# Power.net
KiCad netlist of a schematic drawn in Altium Designer
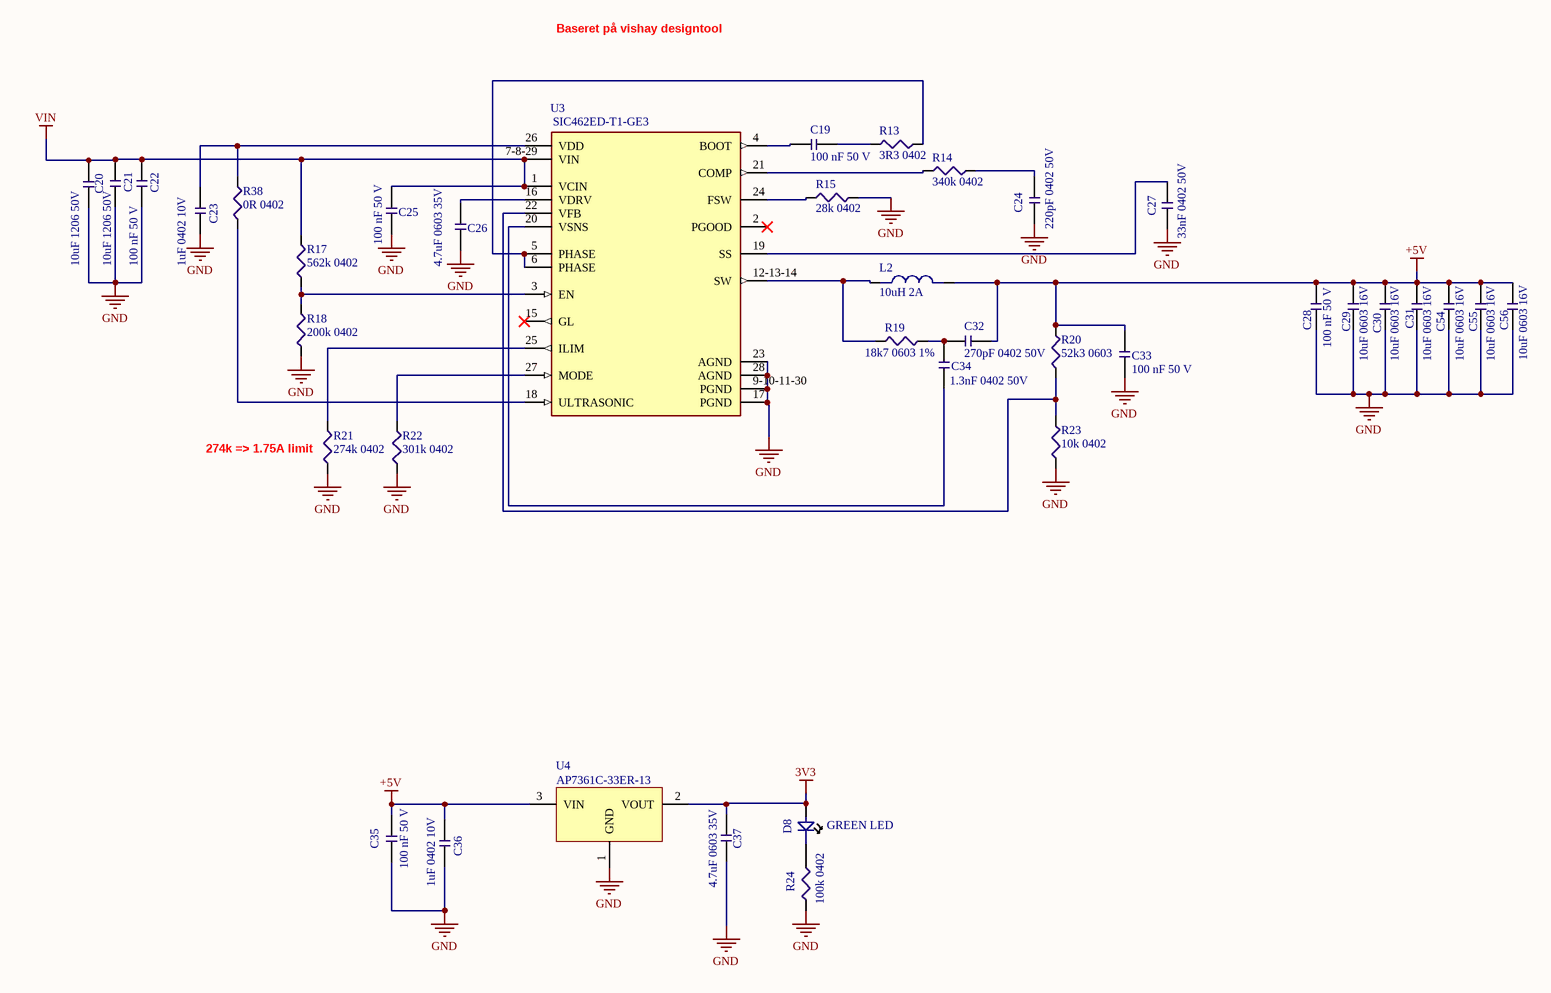
[diagram p0: Power.SchDoc]

(export (version "E")
  (design (tool "Eeschema 10.0.6"))
  (components
    (comp (ref "C19")
      (value "100 nF 50 V")
      (footprint "CAP_0402")
      (description "Multilayer Ceramic Capacitors MLCC - SMD/SMT .1uF 50Volts X7R +/-10% 0402 STD")
      (fields (field (name "TOLERANCE") "10%") (field (name "VOLTAGE") "50 V"))
      (libsource (lib "ON Development Vault") (part "Capacitor"))
    )
    (comp (ref "C20")
      (value "10uF 1206 50V")
      (footprint "CAP_1206")
      (description "10uF 1206 50V X5R 20%")
      (fields (field (name "TOLERANCE") "+/- 20%") (field (name "VOLTAGE") "50 V"))
      (libsource (lib "ON Development Vault") (part "Capacitor"))
    )
    (comp (ref "C21")
      (value "10uF 1206 50V")
      (footprint "CAP_1206")
      (description "10uF 1206 50V X5R 20%")
      (fields (field (name "TOLERANCE") "+/- 20%") (field (name "VOLTAGE") "50 V"))
      (libsource (lib "ON Development Vault") (part "Capacitor"))
    )
    (comp (ref "C22")
      (value "100 nF 50 V")
      (footprint "CAP_0402")
      (description "Multilayer Ceramic Capacitors MLCC - SMD/SMT .1uF 50Volts X7R +/-10% 0402 STD")
      (fields (field (name "TOLERANCE") "10%") (field (name "VOLTAGE") "50 V"))
      (libsource (lib "ON Development Vault") (part "Capacitor"))
    )
    (comp (ref "C23")
      (value "1uF 0402 10V")
      (footprint "CAP_0402")
      (description "1uF 0402 10V 10% X5R")
      (fields (field (name "TOLERANCE") "10%") (field (name "VOLTAGE") "10 V"))
      (libsource (lib "ON Development Vault") (part "Capacitor"))
    )
    (comp (ref "C24")
      (value "220pF 0402 50V")
      (footprint "CAP_0402")
      (description "220pF 0402 50V 5%")
      (fields (field (name "TOLERANCE") "5%") (field (name "VOLTAGE") "50V"))
      (libsource (lib "ON Development Vault") (part "Capacitor"))
    )
    (comp (ref "C25")
      (value "100 nF 50 V")
      (footprint "CAP_0402")
      (description "Multilayer Ceramic Capacitors MLCC - SMD/SMT .1uF 50Volts X7R +/-10% 0402 STD")
      (fields (field (name "TOLERANCE") "10%") (field (name "VOLTAGE") "50 V"))
      (libsource (lib "ON Development Vault") (part "Capacitor"))
    )
    (comp (ref "C26")
      (value "4.7uF 0603 35V")
      (footprint "CAP_0603")
      (fields (field (name "TOLERANCE") "10%"))
      (libsource (lib "ON Development Vault") (part "Capacitor"))
    )
    (comp (ref "C27")
      (value "33nF 0402 50V")
      (footprint "CAP_0402")
      (description "33nF 0402 50V X7R 10%")
      (fields (field (name "TOLERANCE") "10%") (field (name "VOLTAGE") "50V"))
      (libsource (lib "ON Development Vault") (part "Capacitor"))
    )
    (comp (ref "C28")
      (value "100 nF 50 V")
      (footprint "CAP_0402")
      (description "Multilayer Ceramic Capacitors MLCC - SMD/SMT .1uF 50Volts X7R +/-10% 0402 STD")
      (fields (field (name "TOLERANCE") "10%") (field (name "VOLTAGE") "50 V"))
      (libsource (lib "ON Development Vault") (part "Capacitor"))
    )
    (comp (ref "C29")
      (value "10uF 0603 16V")
      (footprint "CAP_0603")
      (description "CAP CER 10UF 16V X5R 0603")
      (fields (field (name "TOLERANCE") "10%") (field (name "VOLTAGE") "16V"))
      (libsource (lib "ON Development Vault") (part "Capacitor"))
    )
    (comp (ref "C30")
      (value "10uF 0603 16V")
      (footprint "CAP_0603")
      (description "CAP CER 10UF 16V X5R 0603")
      (fields (field (name "TOLERANCE") "10%") (field (name "VOLTAGE") "16V"))
      (libsource (lib "ON Development Vault") (part "Capacitor"))
    )
    (comp (ref "C31")
      (value "10uF 0603 16V")
      (footprint "CAP_0603")
      (description "CAP CER 10UF 16V X5R 0603")
      (fields (field (name "TOLERANCE") "10%") (field (name "VOLTAGE") "16V"))
      (libsource (lib "ON Development Vault") (part "Capacitor"))
    )
    (comp (ref "C32")
      (value "270pF 0402 50V")
      (footprint "CAP_0402")
      (description "Multilayer Ceramic Capacitors MLCC - SMD/SMT Midhigh 0402 C0G 50V 270pF 5%")
      (fields (field (name "TOLERANCE") "5%") (field (name "VOLTAGE") "50V"))
      (libsource (lib "ON Development Vault") (part "Capacitor"))
    )
    (comp (ref "C33")
      (value "100 nF 50 V")
      (footprint "CAP_0402")
      (description "Multilayer Ceramic Capacitors MLCC - SMD/SMT .1uF 50Volts X7R +/-10% 0402 STD")
      (fields (field (name "TOLERANCE") "10%") (field (name "VOLTAGE") "50 V"))
      (libsource (lib "ON Development Vault") (part "Capacitor"))
    )
    (comp (ref "C34")
      (value "1.3nF 0402 50V")
      (footprint "CAP_0402")
      (description "Cap Ceramic 0.0013uF 50V C0G 5% SMD 0402 125°C Paper T/R")
      (fields (field (name "TOLERANCE") "10%") (field (name "VOLTAGE") "50V"))
      (libsource (lib "ON Development Vault") (part "Capacitor"))
    )
    (comp (ref "C35")
      (value "100 nF 50 V")
      (footprint "CAP_0402")
      (description "Multilayer Ceramic Capacitors MLCC - SMD/SMT .1uF 50Volts X7R +/-10% 0402 STD")
      (fields (field (name "TOLERANCE") "10%") (field (name "VOLTAGE") "50 V"))
      (libsource (lib "ON Development Vault") (part "Capacitor"))
    )
    (comp (ref "C36")
      (value "1uF 0402 10V")
      (footprint "CAP_0402")
      (description "1uF 0402 10V 10% X5R")
      (fields (field (name "TOLERANCE") "10%") (field (name "VOLTAGE") "10 V"))
      (libsource (lib "ON Development Vault") (part "Capacitor"))
    )
    (comp (ref "C37")
      (value "4.7uF 0603 35V")
      (footprint "CAP_0603")
      (fields (field (name "TOLERANCE") "10%"))
      (libsource (lib "ON Development Vault") (part "Capacitor"))
    )
    (comp (ref "C54")
      (value "10uF 0603 16V")
      (footprint "CAP_0603")
      (description "CAP CER 10UF 16V X5R 0603")
      (fields (field (name "TOLERANCE") "10%") (field (name "VOLTAGE") "16V"))
      (libsource (lib "ON Development Vault") (part "Capacitor"))
    )
    (comp (ref "C55")
      (value "10uF 0603 16V")
      (footprint "CAP_0603")
      (description "CAP CER 10UF 16V X5R 0603")
      (fields (field (name "TOLERANCE") "10%") (field (name "VOLTAGE") "16V"))
      (libsource (lib "ON Development Vault") (part "Capacitor"))
    )
    (comp (ref "C56")
      (value "10uF 0603 16V")
      (footprint "CAP_0603")
      (description "CAP CER 10UF 16V X5R 0603")
      (fields (field (name "TOLERANCE") "10%") (field (name "VOLTAGE") "16V"))
      (libsource (lib "ON Development Vault") (part "Capacitor"))
    )
    (comp (ref "D8")
      (value "GREEN LED")
      (footprint "0402 LED")
      (description "0402 SMD LED")
      (fields (field (name "MFG. PART NUMBER") "LTST-C281KGKT"))
      (libsource (lib "ON Development Vault") (part "LED"))
    )
    (comp (ref "L2")
      (value "10uH 2A")
      (footprint "FP-NR5040-H_4_1-MFG")
      (description "Inductor Power Shielded Wirewound 10uH 20% 100KHz Ferrite 2.1A 0.0728Ohm DCR T/R")
      (fields (field (name "MFG. PART NO") "NRS5040T100MMGJ"))
      (libsource (lib "ON Development Vault") (part "Inductor"))
    )
    (comp (ref "R13")
      (value "3R3 0402")
      (footprint "RES_0402")
      (description "RES SMD 3R3 OHM 1% 1/16W 0402")
      (fields (field (name "POWER") "1/16 W") (field (name "TOLERANCE") "5%"))
      (libsource (lib "ON Development Vault") (part "Resistor"))
    )
    (comp (ref "R14")
      (value "340k 0402")
      (footprint "RES_0402")
      (description "RES SMD 340K OHM 1% 1/16W 0402")
      (fields (field (name "POWER") "1/16 W") (field (name "TOLERANCE") "1%"))
      (libsource (lib "ON Development Vault") (part "Resistor"))
    )
    (comp (ref "R15")
      (value "28k 0402")
      (footprint "RES_0402")
      (description "28K 0402 1% 1/16W")
      (fields (field (name "POWER") "1/16W") (field (name "TOLERANCE") "1%"))
      (libsource (lib "ON Development Vault") (part "Resistor"))
    )
    (comp (ref "R17")
      (value "562k 0402")
      (footprint "RES_0402")
      (description "RES SMD 562K OHM 1% 1/16W 0402")
      (fields (field (name "POWER") "1/16 W") (field (name "TOLERANCE") "1%"))
      (libsource (lib "ON Development Vault") (part "Resistor"))
    )
    (comp (ref "R18")
      (value "200k 0402")
      (footprint "RES_0402")
      (description "RES SMD 200K OHM 1% 1/16W 0402")
      (fields (field (name "POWER") "1/16 W") (field (name "TOLERANCE") "1%"))
      (libsource (lib "ON Development Vault") (part "Resistor"))
    )
    (comp (ref "R19")
      (value "18k7 0603 1%")
      (footprint "RES_0603")
      (description "Res Thick Film 0603 18.7K Ohm 1% 1/10W ±100ppm/°C Molded SMD SMD Paper T/R")
      (fields (field (name "TOLERANCE") "1%") (field (name "MANUFACTURER PART NO.") "RMCF0603FT18K7"))
      (libsource (lib "ON Development Vault") (part "Resistor"))
    )
    (comp (ref "R20")
      (value "52k3 0603")
      (footprint "RES_0603")
      (description "Res Thick Film 0603 52.3K Ohm 1% 0.1W(1/10W) ±100ppm/C Epoxy SMD T/R")
      (fields (field (name "POWER") "1/10W") (field (name "TOLERANCE") "1%"))
      (libsource (lib "ON Development Vault") (part "Resistor"))
    )
    (comp (ref "R21")
      (value "274k 0402")
      (footprint "RES_0402")
      (description "Res Thick Film 0402 274K Ohm 1% 0.063W ±100ppm/°C Molded SMD Paper T/R")
      (fields (field (name "POWER") "63mW") (field (name "TOLERANCE") "1%"))
      (libsource (lib "ON Development Vault") (part "Resistor"))
    )
    (comp (ref "R22")
      (value "301k 0402")
      (footprint "RES_0402")
      (description "301K 1% 0402")
      (fields (field (name "TOLERANCE") "1%") (field (name "MANUFACTURER PART NO.") "RMCF0402FT301K"))
      (libsource (lib "ON Development Vault") (part "Resistor"))
    )
    (comp (ref "R23")
      (value "10k 0402")
      (footprint "RES_0402")
      (description "RES SMD 10K OHM 1% 1/16W 0402")
      (fields (field (name "POWER") "1/16 W") (field (name "TOLERANCE") "1 %"))
      (libsource (lib "ON Development Vault") (part "Resistor"))
    )
    (comp (ref "R24")
      (value "100k 0402")
      (footprint "RES_0402")
      (description "Res General Purpose Thick Film 0402 100K Ohm 1% 1/16W ±100ppm/°C Molded SMD Paper T/R")
      (fields (field (name "TOLERANCE") "1%") (field (name "VOLTAGE") "50V"))
      (libsource (lib "ON Development Vault") (part "Resistor"))
    )
    (comp (ref "R38")
      (value "0R 0402")
      (footprint "RES_0402")
      (description "RES SMD 0 OHM 1/16W 0402")
      (fields (field (name "POWER") "63mW") (field (name "MFG. PART NUMBER") "RC0402JR-070RL"))
      (libsource (lib "ON Development Vault") (part "Resistor"))
    )
    (comp (ref "U3")
      (value "SIC462ED-T1-GE3")
      (footprint "FP-T18-0594-MFG")
      (description "SiC462 Series 60 V 6 A Synchronous Buck Regulator - PowerPAK® MLP55-27")
      (libsource (lib "ON Development Vault") (part "92a46bbdb5b7b3ea9c407102cc13196"))
    )
    (comp (ref "U4")
      (value "AP7361C-33ER-13")
      (footprint "SOT230P700X180-4N")
      (description "1A Low Dropout 3V3")
      (libsource (lib "ON Development Vault") (part "AZ1117CH"))
    )
  )
  (nets
    (net (code "1") (name "+5V") (class "Default")
      (node (ref "C28") (pin "2") (pinfunction "2_2") (pintype "passive"))
      (node (ref "C29") (pin "2") (pinfunction "2_2") (pintype "passive"))
      (node (ref "C30") (pin "2") (pinfunction "2_2") (pintype "passive"))
      (node (ref "C31") (pin "2") (pinfunction "2_2") (pintype "passive"))
      (node (ref "C32") (pin "2") (pinfunction "2_2") (pintype "passive"))
      (node (ref "C33") (pin "2") (pinfunction "2_2") (pintype "passive"))
      (node (ref "C35") (pin "2") (pinfunction "2_2") (pintype "passive"))
      (node (ref "C36") (pin "2") (pinfunction "2_2") (pintype "passive"))
      (node (ref "C54") (pin "2") (pinfunction "2_2") (pintype "passive"))
      (node (ref "C55") (pin "2") (pinfunction "2_2") (pintype "passive"))
      (node (ref "C56") (pin "2") (pinfunction "2_2") (pintype "passive"))
      (node (ref "L2") (pin "2") (pinfunction "2_2") (pintype "passive"))
      (node (ref "R20") (pin "2") (pinfunction "2_2") (pintype "passive"))
      (node (ref "U4") (pin "3") (pinfunction "VIN_3") (pintype "passive"))
    )
    (net (code "2") (name "3V3") (class "Default")
      (node (ref "C37") (pin "2") (pinfunction "2_2") (pintype "passive"))
      (node (ref "D8") (pin "1") (pinfunction "1_1") (pintype "passive"))
      (node (ref "U4") (pin "2") (pinfunction "VOUT_2") (pintype "passive"))
    )
    (net (code "3") (name "GND") (class "Default")
      (node (ref "C20") (pin "2") (pinfunction "2_2") (pintype "passive"))
      (node (ref "C21") (pin "2") (pinfunction "2_2") (pintype "passive"))
      (node (ref "C22") (pin "1") (pinfunction "1_1") (pintype "passive"))
      (node (ref "C23") (pin "1") (pinfunction "1_1") (pintype "passive"))
      (node (ref "C24") (pin "1") (pinfunction "1_1") (pintype "passive"))
      (node (ref "C25") (pin "1") (pinfunction "1_1") (pintype "passive"))
      (node (ref "C26") (pin "1") (pinfunction "1_1") (pintype "passive"))
      (node (ref "C27") (pin "1") (pinfunction "1_1") (pintype "passive"))
      (node (ref "C28") (pin "1") (pinfunction "1_1") (pintype "passive"))
      (node (ref "C29") (pin "1") (pinfunction "1_1") (pintype "passive"))
      (node (ref "C30") (pin "1") (pinfunction "1_1") (pintype "passive"))
      (node (ref "C31") (pin "1") (pinfunction "1_1") (pintype "passive"))
      (node (ref "C33") (pin "1") (pinfunction "1_1") (pintype "passive"))
      (node (ref "C35") (pin "1") (pinfunction "1_1") (pintype "passive"))
      (node (ref "C36") (pin "1") (pinfunction "1_1") (pintype "passive"))
      (node (ref "C37") (pin "1") (pinfunction "1_1") (pintype "passive"))
      (node (ref "C54") (pin "1") (pinfunction "1_1") (pintype "passive"))
      (node (ref "C55") (pin "1") (pinfunction "1_1") (pintype "passive"))
      (node (ref "C56") (pin "1") (pinfunction "1_1") (pintype "passive"))
      (node (ref "R15") (pin "2") (pinfunction "2_2") (pintype "passive"))
      (node (ref "R18") (pin "1") (pinfunction "1_1") (pintype "passive"))
      (node (ref "R21") (pin "1") (pinfunction "1_1") (pintype "passive"))
      (node (ref "R22") (pin "1") (pinfunction "1_1") (pintype "passive"))
      (node (ref "R23") (pin "1") (pinfunction "1_1") (pintype "passive"))
      (node (ref "R24") (pin "1") (pinfunction "1_1") (pintype "passive"))
      (node (ref "U3") (pin "17") (pinfunction "PGND_17") (pintype "power_in"))
      (node (ref "U3") (pin "23") (pinfunction "AGND_23") (pintype "power_in"))
      (node (ref "U3") (pin "28") (pinfunction "AGND_28") (pintype "power_in"))
      (node (ref "U3") (pin "9-10-11-30") (pinfunction "PGND_9-10-11-30") (pintype "power_in"))
      (node (ref "U4") (pin "1") (pinfunction "GND_1") (pintype "passive"))
    )
    (net (code "4") (name "Net-(C19-Pad2)") (class "Default")
      (node (ref "C19") (pin "2") (pinfunction "2_2") (pintype "passive"))
      (node (ref "R13") (pin "1") (pinfunction "1_1") (pintype "passive"))
    )
    (net (code "5") (name "Net-(C24-Pad2)") (class "Default")
      (node (ref "C24") (pin "2") (pinfunction "2_2") (pintype "passive"))
      (node (ref "R14") (pin "2") (pinfunction "2_2") (pintype "passive"))
    )
    (net (code "6") (name "Net-(C32-Pad1)") (class "Default")
      (node (ref "C32") (pin "1") (pinfunction "1_1") (pintype "passive"))
      (node (ref "C34") (pin "2") (pinfunction "2_2") (pintype "passive"))
      (node (ref "R19") (pin "2") (pinfunction "2_2") (pintype "passive"))
    )
    (net (code "7") (name "Net-(D8-Pad2)") (class "Default")
      (node (ref "D8") (pin "2") (pinfunction "2_2") (pintype "passive"))
      (node (ref "R24") (pin "2") (pinfunction "2_2") (pintype "passive"))
    )
    (net (code "8") (name "Net-(R13-Pad2)") (class "Default")
      (node (ref "R13") (pin "2") (pinfunction "2_2") (pintype "passive"))
      (node (ref "U3") (pin "5") (pinfunction "PHASE_5") (pintype "passive"))
      (node (ref "U3") (pin "6") (pinfunction "PHASE_6") (pintype "passive"))
    )
    (net (code "9") (name "Net-(U3-BOOT)") (class "Default")
      (node (ref "C19") (pin "1") (pinfunction "1_1") (pintype "passive"))
      (node (ref "U3") (pin "4") (pinfunction "BOOT_4") (pintype "output"))
    )
    (net (code "10") (name "Net-(U3-COMP)") (class "Default")
      (node (ref "R14") (pin "1") (pinfunction "1_1") (pintype "passive"))
      (node (ref "U3") (pin "21") (pinfunction "COMP_21") (pintype "output"))
    )
    (net (code "11") (name "Net-(U3-EN)") (class "Default")
      (node (ref "R17") (pin "1") (pinfunction "1_1") (pintype "passive"))
      (node (ref "R18") (pin "2") (pinfunction "2_2") (pintype "passive"))
      (node (ref "U3") (pin "3") (pinfunction "EN_3") (pintype "input"))
    )
    (net (code "12") (name "Net-(U3-FSW)") (class "Default")
      (node (ref "R15") (pin "1") (pinfunction "1_1") (pintype "passive"))
      (node (ref "U3") (pin "24") (pinfunction "FSW_24") (pintype "passive"))
    )
    (net (code "13") (name "Net-(U3-ILIM)") (class "Default")
      (node (ref "R21") (pin "2") (pinfunction "2_2") (pintype "passive"))
      (node (ref "U3") (pin "25") (pinfunction "ILIM_25") (pintype "output"))
    )
    (net (code "14") (name "Net-(U3-MODE)") (class "Default")
      (node (ref "R22") (pin "2") (pinfunction "2_2") (pintype "passive"))
      (node (ref "U3") (pin "27") (pinfunction "MODE_27") (pintype "input"))
    )
    (net (code "15") (name "Net-(U3-SS)") (class "Default")
      (node (ref "C27") (pin "2") (pinfunction "2_2") (pintype "passive"))
      (node (ref "U3") (pin "19") (pinfunction "SS_19") (pintype "passive"))
    )
    (net (code "16") (name "Net-(U3-SW)") (class "Default")
      (node (ref "L2") (pin "1") (pinfunction "1_1") (pintype "passive"))
      (node (ref "R19") (pin "1") (pinfunction "1_1") (pintype "passive"))
      (node (ref "U3") (pin "12-13-14") (pinfunction "SW_12-13-14") (pintype "output"))
    )
    (net (code "17") (name "Net-(U3-ULTRASONIC)") (class "Default")
      (node (ref "R38") (pin "1") (pinfunction "1_1") (pintype "passive"))
      (node (ref "U3") (pin "18") (pinfunction "ULTRASONIC_18") (pintype "input"))
    )
    (net (code "18") (name "Net-(U3-VDD)") (class "Default")
      (node (ref "C23") (pin "2") (pinfunction "2_2") (pintype "passive"))
      (node (ref "R38") (pin "2") (pinfunction "2_2") (pintype "passive"))
      (node (ref "U3") (pin "26") (pinfunction "VDD_26") (pintype "power_in"))
    )
    (net (code "19") (name "Net-(U3-VDRV)") (class "Default")
      (node (ref "C26") (pin "2") (pinfunction "2_2") (pintype "passive"))
      (node (ref "U3") (pin "16") (pinfunction "VDRV_16") (pintype "power_in"))
    )
    (net (code "20") (name "Net-(U3-VFB)") (class "Default")
      (node (ref "R20") (pin "1") (pinfunction "1_1") (pintype "passive"))
      (node (ref "R23") (pin "2") (pinfunction "2_2") (pintype "passive"))
      (node (ref "U3") (pin "22") (pinfunction "VFB_22") (pintype "passive"))
    )
    (net (code "21") (name "Net-(U3-VSNS)") (class "Default")
      (node (ref "C34") (pin "1") (pinfunction "1_1") (pintype "passive"))
      (node (ref "U3") (pin "20") (pinfunction "VSNS_20") (pintype "power_in"))
    )
    (net (code "22") (name "VIN") (class "Default")
      (node (ref "C20") (pin "1") (pinfunction "1_1") (pintype "passive"))
      (node (ref "C21") (pin "1") (pinfunction "1_1") (pintype "passive"))
      (node (ref "C22") (pin "2") (pinfunction "2_2") (pintype "passive"))
      (node (ref "C25") (pin "2") (pinfunction "2_2") (pintype "passive"))
      (node (ref "R17") (pin "2") (pinfunction "2_2") (pintype "passive"))
      (node (ref "U3") (pin "1") (pinfunction "VCIN_1") (pintype "power_in"))
      (node (ref "U3") (pin "7-8-29") (pinfunction "VIN_7-8-29") (pintype "power_in"))
    )
    (net (code "23") (name "unconnected-(U3-GL-Pad15)") (class "Default")
      (node (ref "U3") (pin "15") (pinfunction "GL_15") (pintype "output+no_connect"))
    )
    (net (code "24") (name "unconnected-(U3-PGOOD-Pad2)") (class "Default")
      (node (ref "U3") (pin "2") (pinfunction "PGOOD_2") (pintype "open_collector+no_connect"))
    )
  )
)
